# AT85_Power_SW_01A_H1_0.net
KiCad netlist of a schematic drawn in EAGLE
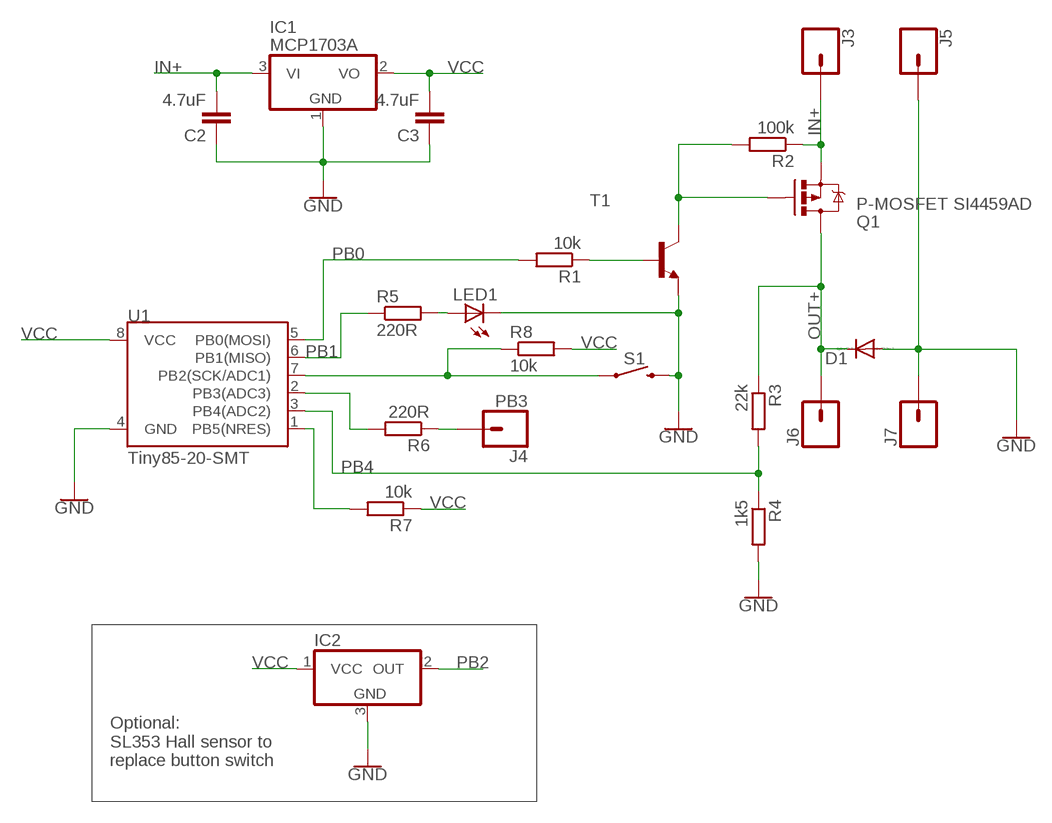
[diagram p0: schematic, sheet 1]

(export (version "E")
  (design (tool "Eeschema 10.0.6"))
  (components
    (comp (ref "C2")
      (value "4.7uF")
      (footprint "eagle-import:C0805")
      (libsource (lib "eagle-import") (part "CAP_SMD_C0805"))
    )
    (comp (ref "C3")
      (value "4.7uF")
      (footprint "eagle-import:C0805")
      (libsource (lib "eagle-import") (part "CAP_SMD_C0805"))
    )
    (comp (ref "D1")
      (value "DIODE-DO-214AC")
      (footprint "eagle-import:DO-214AC")
      (libsource (lib "eagle-import") (part "DIODE-DO-214AC"))
    )
    (comp (ref "IC1")
      (value "MCP1703A")
      (footprint "eagle-import:SOT23")
      (libsource (lib "eagle-import") (part "MCP1703CB"))
    )
    (comp (ref "IC2")
      (value "SL353")
      (footprint "eagle-import:SOT23")
      (libsource (lib "eagle-import") (part "SL353"))
    )
    (comp (ref "J3")
      (value "CONN_01PTH_LONGPAD")
      (footprint "eagle-import:1X01_LONGPAD")
      (libsource (lib "eagle-import") (part "CONN_01PTH_LONGPAD"))
    )
    (comp (ref "J4")
      (value "PB3")
      (footprint "eagle-import:1X01")
      (libsource (lib "eagle-import") (part "CONN_01"))
    )
    (comp (ref "J5")
      (value "CONN_01PTH_LONGPAD")
      (footprint "eagle-import:1X01_LONGPAD")
      (libsource (lib "eagle-import") (part "CONN_01PTH_LONGPAD"))
    )
    (comp (ref "J6")
      (value "CONN_01PTH_LONGPAD")
      (footprint "eagle-import:1X01_LONGPAD")
      (libsource (lib "eagle-import") (part "CONN_01PTH_LONGPAD"))
    )
    (comp (ref "J7")
      (value "CONN_01PTH_LONGPAD")
      (footprint "eagle-import:1X01_LONGPAD")
      (libsource (lib "eagle-import") (part "CONN_01PTH_LONGPAD"))
    )
    (comp (ref "LED1")
      (value "LED3MM")
      (footprint "eagle-import:LED3MM")
      (libsource (lib "eagle-import") (part "LED3MM"))
    )
    (comp (ref "Q1")
      (value "P-MOSFET SI4459AD")
      (footprint "eagle-import:SO08")
      (libsource (lib "eagle-import") (part "MOSFET-PCHANNELFDS6675"))
    )
    (comp (ref "R1")
      (value "10k")
      (footprint "eagle-import:R0805")
      (libsource (lib "eagle-import") (part "RESISTOR_SMDR0805"))
    )
    (comp (ref "R2")
      (value "100k")
      (footprint "eagle-import:R0805")
      (libsource (lib "eagle-import") (part "RESISTOR_SMDR0805"))
    )
    (comp (ref "R3")
      (value "22k")
      (footprint "eagle-import:R0805")
      (libsource (lib "eagle-import") (part "RESISTOR_SMDR0805"))
    )
    (comp (ref "R4")
      (value "1k5")
      (footprint "eagle-import:R0805")
      (libsource (lib "eagle-import") (part "RESISTOR_SMDR0805"))
    )
    (comp (ref "R5")
      (value "220R")
      (footprint "eagle-import:R0805")
      (libsource (lib "eagle-import") (part "RESISTOR_SMDR0805"))
    )
    (comp (ref "R6")
      (value "220R")
      (footprint "eagle-import:R0805")
      (libsource (lib "eagle-import") (part "RESISTOR_SMDR0805"))
    )
    (comp (ref "R7")
      (value "10k")
      (footprint "eagle-import:R0805")
      (libsource (lib "eagle-import") (part "RESISTOR_SMDR0805"))
    )
    (comp (ref "R8")
      (value "10k")
      (footprint "eagle-import:R0805")
      (libsource (lib "eagle-import") (part "RESISTOR_SMDR0805"))
    )
    (comp (ref "S1")
      (value "MOMENTARY-SWITCH-SPST-SMD-6.2MM-TALL")
      (footprint "eagle-import:TACTILE_SWITCH_SMD_6.2MM_TALL")
      (libsource (lib "eagle-import") (part "MOMENTARY-SWITCH-SPST-SMD-6.2MM-TALL"))
    )
    (comp (ref "T1")
      (value "MMBT2222ALT1-NPN-SOT23-BEC")
      (footprint "eagle-import:SOT23-BEC")
      (libsource (lib "eagle-import") (part "-NPN-SOT23-BECMMBT2222ALT1"))
    )
    (comp (ref "U1")
      (value "Tiny85-20-SMT")
      (footprint "eagle-import:SO08-EIAJ_MCU")
      (libsource (lib "eagle-import") (part "ATTINY45TINY85-20-SMT"))
    )
  )
  (nets
    (net (code "1") (name "/IN+") (class "Default")
      (node (ref "C2") (pin "2") (pinfunction "2_2") (pintype "passive"))
      (node (ref "IC1") (pin "3") (pinfunction "VI_3") (pintype "input"))
      (node (ref "J3") (pin "1") (pinfunction "1_1") (pintype "passive"))
      (node (ref "Q1") (pin "1") (pinfunction "S_1") (pintype "passive"))
      (node (ref "Q1") (pin "2") (pinfunction "S_2") (pintype "passive"))
      (node (ref "Q1") (pin "3") (pinfunction "S_3") (pintype "passive"))
      (node (ref "R2") (pin "1") (pinfunction "1_1") (pintype "passive"))
    )
    (net (code "2") (name "/OUT+") (class "Default")
      (node (ref "D1") (pin "C") (pinfunction "C_C") (pintype "passive"))
      (node (ref "J6") (pin "1") (pinfunction "1_1") (pintype "passive"))
      (node (ref "Q1") (pin "5") (pinfunction "D_5") (pintype "passive"))
      (node (ref "Q1") (pin "6") (pinfunction "D_6") (pintype "passive"))
      (node (ref "Q1") (pin "7") (pinfunction "D_7") (pintype "passive"))
      (node (ref "Q1") (pin "8") (pinfunction "D_8") (pintype "passive"))
      (node (ref "R3") (pin "1") (pinfunction "1_1") (pintype "passive"))
    )
    (net (code "3") (name "/PB0") (class "Default")
      (node (ref "R1") (pin "2") (pinfunction "2_2") (pintype "passive"))
      (node (ref "U1") (pin "5") (pinfunction "PB0(MOSI)_5") (pintype "bidirectional"))
    )
    (net (code "4") (name "/PB1") (class "Default")
      (node (ref "R5") (pin "1") (pinfunction "1_1") (pintype "passive"))
      (node (ref "U1") (pin "6") (pinfunction "PB1(MISO)_6") (pintype "bidirectional"))
    )
    (net (code "5") (name "/PB2") (class "Default")
      (node (ref "IC2") (pin "2") (pinfunction "OUT_2") (pintype "passive"))
      (node (ref "R8") (pin "1") (pinfunction "1_1") (pintype "passive"))
      (node (ref "S1") (pin "A2") (pinfunction "1_A2") (pintype "passive"))
      (node (ref "U1") (pin "7") (pinfunction "PB2(SCK/ADC1)_7") (pintype "bidirectional"))
    )
    (net (code "6") (name "/PB4") (class "Default")
      (node (ref "R3") (pin "2") (pinfunction "2_2") (pintype "passive"))
      (node (ref "R4") (pin "1") (pinfunction "1_1") (pintype "passive"))
      (node (ref "U1") (pin "3") (pinfunction "PB4(ADC2)_3") (pintype "bidirectional"))
    )
    (net (code "7") (name "/VCC") (class "Default")
      (node (ref "C3") (pin "2") (pinfunction "2_2") (pintype "passive"))
      (node (ref "IC1") (pin "2") (pinfunction "VO_2") (pintype "passive"))
      (node (ref "IC2") (pin "1") (pinfunction "VCC_1") (pintype "input"))
      (node (ref "R7") (pin "1") (pinfunction "1_1") (pintype "passive"))
      (node (ref "R8") (pin "2") (pinfunction "2_2") (pintype "passive"))
      (node (ref "U1") (pin "8") (pinfunction "VCC_8") (pintype "bidirectional"))
    )
    (net (code "8") (name "GND") (class "Default")
      (node (ref "C2") (pin "1") (pinfunction "1_1") (pintype "passive"))
      (node (ref "C3") (pin "1") (pinfunction "1_1") (pintype "passive"))
      (node (ref "D1") (pin "A") (pinfunction "A_A") (pintype "passive"))
      (node (ref "IC1") (pin "1") (pinfunction "GND_1") (pintype "passive"))
      (node (ref "IC2") (pin "3") (pinfunction "GND_3") (pintype "passive"))
      (node (ref "J5") (pin "1") (pinfunction "1_1") (pintype "passive"))
      (node (ref "J7") (pin "1") (pinfunction "1_1") (pintype "passive"))
      (node (ref "LED1") (pin "K") (pinfunction "C_K") (pintype "passive"))
      (node (ref "R4") (pin "2") (pinfunction "2_2") (pintype "passive"))
      (node (ref "S1") (pin "B2") (pinfunction "2_B2") (pintype "passive"))
      (node (ref "T1") (pin "E") (pinfunction "E_E") (pintype "passive"))
      (node (ref "U1") (pin "4") (pinfunction "GND_4") (pintype "bidirectional"))
    )
    (net (code "9") (name "Net-(J4-Pad1)") (class "Default")
      (node (ref "J4") (pin "1") (pinfunction "1_1") (pintype "passive"))
      (node (ref "R6") (pin "1") (pinfunction "1_1") (pintype "passive"))
    )
    (net (code "10") (name "Net-(LED1-PadA)") (class "Default")
      (node (ref "LED1") (pin "A") (pinfunction "A_A") (pintype "passive"))
      (node (ref "R5") (pin "2") (pinfunction "2_2") (pintype "passive"))
    )
    (net (code "11") (name "Net-(Q1-G)") (class "Default")
      (node (ref "Q1") (pin "4") (pinfunction "G_4") (pintype "passive"))
      (node (ref "R2") (pin "2") (pinfunction "2_2") (pintype "passive"))
      (node (ref "T1") (pin "C") (pinfunction "C_C") (pintype "passive"))
    )
    (net (code "12") (name "Net-(R1-Pad1)") (class "Default")
      (node (ref "R1") (pin "1") (pinfunction "1_1") (pintype "passive"))
      (node (ref "T1") (pin "B") (pinfunction "B_B") (pintype "passive"))
    )
    (net (code "13") (name "Net-(U1-PB3(ADC3))") (class "Default")
      (node (ref "R6") (pin "2") (pinfunction "2_2") (pintype "passive"))
      (node (ref "U1") (pin "2") (pinfunction "PB3(ADC3)_2") (pintype "bidirectional"))
    )
    (net (code "14") (name "Net-(U1-PB5(NRES))") (class "Default")
      (node (ref "R7") (pin "2") (pinfunction "2_2") (pintype "passive"))
      (node (ref "U1") (pin "1") (pinfunction "PB5(NRES)_1") (pintype "bidirectional"))
    )
  )
)
